# SWITCH.net
KiCad netlist of a schematic drawn in Altium Designer
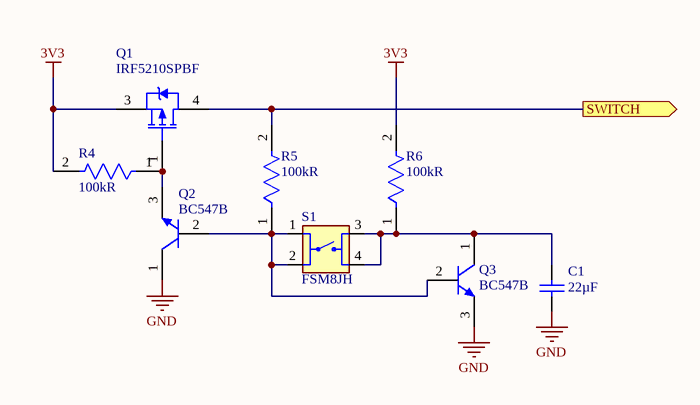
[diagram p0: SWITCH.SchDoc]

(export (version "E")
  (design (tool "Eeschema 10.0.6"))
  (components
    (comp (ref "C1")
      (value "C1608X5R1A226M080AC")
      (footprint "CAPC1608X100X20ML10")
      (description "Chip Capacitor, 22 uF, +/- 20%, 10 V, -55 to 85 degC, 0603 (1608 Metric), RoHS, Tape and Reel")
      (fields
        (field (name "MANUFACTURER") "TDK")
        (field (name "TOLERANCE") "±20%")
        (field (name "CAPACITANCE") "22µF")
      )
      (libsource (lib "Altium Content Vault") (part "CAP-NP-2"))
    )
    (comp (ref "Q1")
      (value "IRF5210SPBF")
      (footprint "INTR-TO-263-3_L")
      (description "HEXFET(R) Power MOSFET, 3.1 W, 63 ns, -55 to 150 degC, 3-Pin DPAK (TO-263AB), RoHS, Tube")
      (fields (field (name "MANUFACTURER") "International Rectifier"))
      (libsource (lib "Altium Content Vault") (part "PEMOS-GSD-3_E"))
    )
    (comp (ref "Q2")
      (value "BC547B")
      (footprint "ONSC-TO-92-3-29-11")
      (description "Amplifier Transistor, NPN Silicon, 3-Pin TO-92, Bulk Box")
      (fields (field (name "MANUFACTURER") "On Semiconductor"))
      (libsource (lib "Altium Content Vault") (part "ONSC-NPN-C1B2E3-3"))
    )
    (comp (ref "Q3")
      (value "BC547B")
      (footprint "ONSC-TO-92-3-29-11")
      (description "Amplifier Transistor, NPN Silicon, 3-Pin TO-92, Bulk Box")
      (fields (field (name "MANUFACTURER") "On Semiconductor"))
      (libsource (lib "Altium Content Vault") (part "ONSC-NPN-C1B2E3-3"))
    )
    (comp (ref "R4")
      (value "RK73H1JLTD1003F")
      (footprint "FP-RK73H1J-IPC_C")
      (description "100kΩ ±1% 0.1W Chip Resistor 0603 Thick Film AEC-Q200 Qualified")
      (fields (field (name "TOLERANCE") "1%") (field (name "RESISTANCE") "100kR"))
      (libsource (lib "Altium Content Vault") (part "1029c3af85768c4190bb7ad29bc67b5"))
    )
    (comp (ref "R5")
      (value "RK73H1JLTD1003F")
      (footprint "FP-RK73H1J-IPC_C")
      (description "100kΩ ±1% 0.1W Chip Resistor 0603 Thick Film AEC-Q200 Qualified")
      (fields (field (name "TOLERANCE") "1%") (field (name "RESISTANCE") "100kR"))
      (libsource (lib "Altium Content Vault") (part "1029c3af85768c4190bb7ad29bc67b5"))
    )
    (comp (ref "R6")
      (value "RK73H1JLTD1003F")
      (footprint "FP-RK73H1J-IPC_C")
      (description "100kΩ ±1% 0.1W Chip Resistor 0603 Thick Film AEC-Q200 Qualified")
      (fields (field (name "TOLERANCE") "1%") (field (name "RESISTANCE") "100kR"))
      (libsource (lib "Altium Content Vault") (part "1029c3af85768c4190bb7ad29bc67b5"))
    )
    (comp (ref "S1")
      (value "FSM8JH")
      (footprint "SW_FSM8JH")
      (description "Switch, Pushbutton, Tactile, SPST, Thru Hole, Vertical, 6MM, Black")
      (libsource (lib "KVM Library") (part "FSM8JH"))
    )
  )
  (nets
    (net (code "1") (name "/SWITCH") (class "Default")
      (node (ref "Q1") (pin "4") (pinfunction "DRAIN_4") (pintype "passive"))
      (node (ref "R5") (pin "2") (pinfunction "2_2") (pintype "passive"))
    )
    (net (code "2") (name "3V3") (class "Default")
      (node (ref "Q1") (pin "3") (pinfunction "SOURCE_3") (pintype "passive"))
      (node (ref "R4") (pin "2") (pinfunction "2_2") (pintype "passive"))
      (node (ref "R6") (pin "2") (pinfunction "2_2") (pintype "passive"))
    )
    (net (code "3") (name "GND") (class "Default")
      (node (ref "C1") (pin "1") (pinfunction "1_1") (pintype "passive"))
      (node (ref "Q2") (pin "1") (pinfunction "C_1") (pintype "passive"))
      (node (ref "Q3") (pin "3") (pinfunction "E_3") (pintype "passive"))
    )
    (net (code "4") (name "Net-(Q1-GATE)") (class "Default")
      (node (ref "Q1") (pin "1") (pinfunction "GATE_1") (pintype "passive"))
      (node (ref "Q2") (pin "3") (pinfunction "E_3") (pintype "passive"))
      (node (ref "R4") (pin "1") (pinfunction "1_1") (pintype "passive"))
    )
    (net (code "5") (name "Net-(Q2-B)") (class "Default")
      (node (ref "Q2") (pin "2") (pinfunction "B_2") (pintype "passive"))
      (node (ref "Q3") (pin "2") (pinfunction "B_2") (pintype "passive"))
      (node (ref "R5") (pin "1") (pinfunction "1_1") (pintype "passive"))
      (node (ref "S1") (pin "1") (pinfunction "1_1") (pintype "passive"))
      (node (ref "S1") (pin "2") (pinfunction "2_2") (pintype "passive"))
    )
    (net (code "6") (name "Net-(Q3-C)") (class "Default")
      (node (ref "C1") (pin "2") (pinfunction "2_2") (pintype "passive"))
      (node (ref "Q3") (pin "1") (pinfunction "C_1") (pintype "passive"))
      (node (ref "R6") (pin "1") (pinfunction "1_1") (pintype "passive"))
      (node (ref "S1") (pin "3") (pinfunction "3_3") (pintype "passive"))
      (node (ref "S1") (pin "4") (pinfunction "4_4") (pintype "passive"))
    )
  )
)
